# Power.net
KiCad netlist of a schematic drawn in Altium Designer
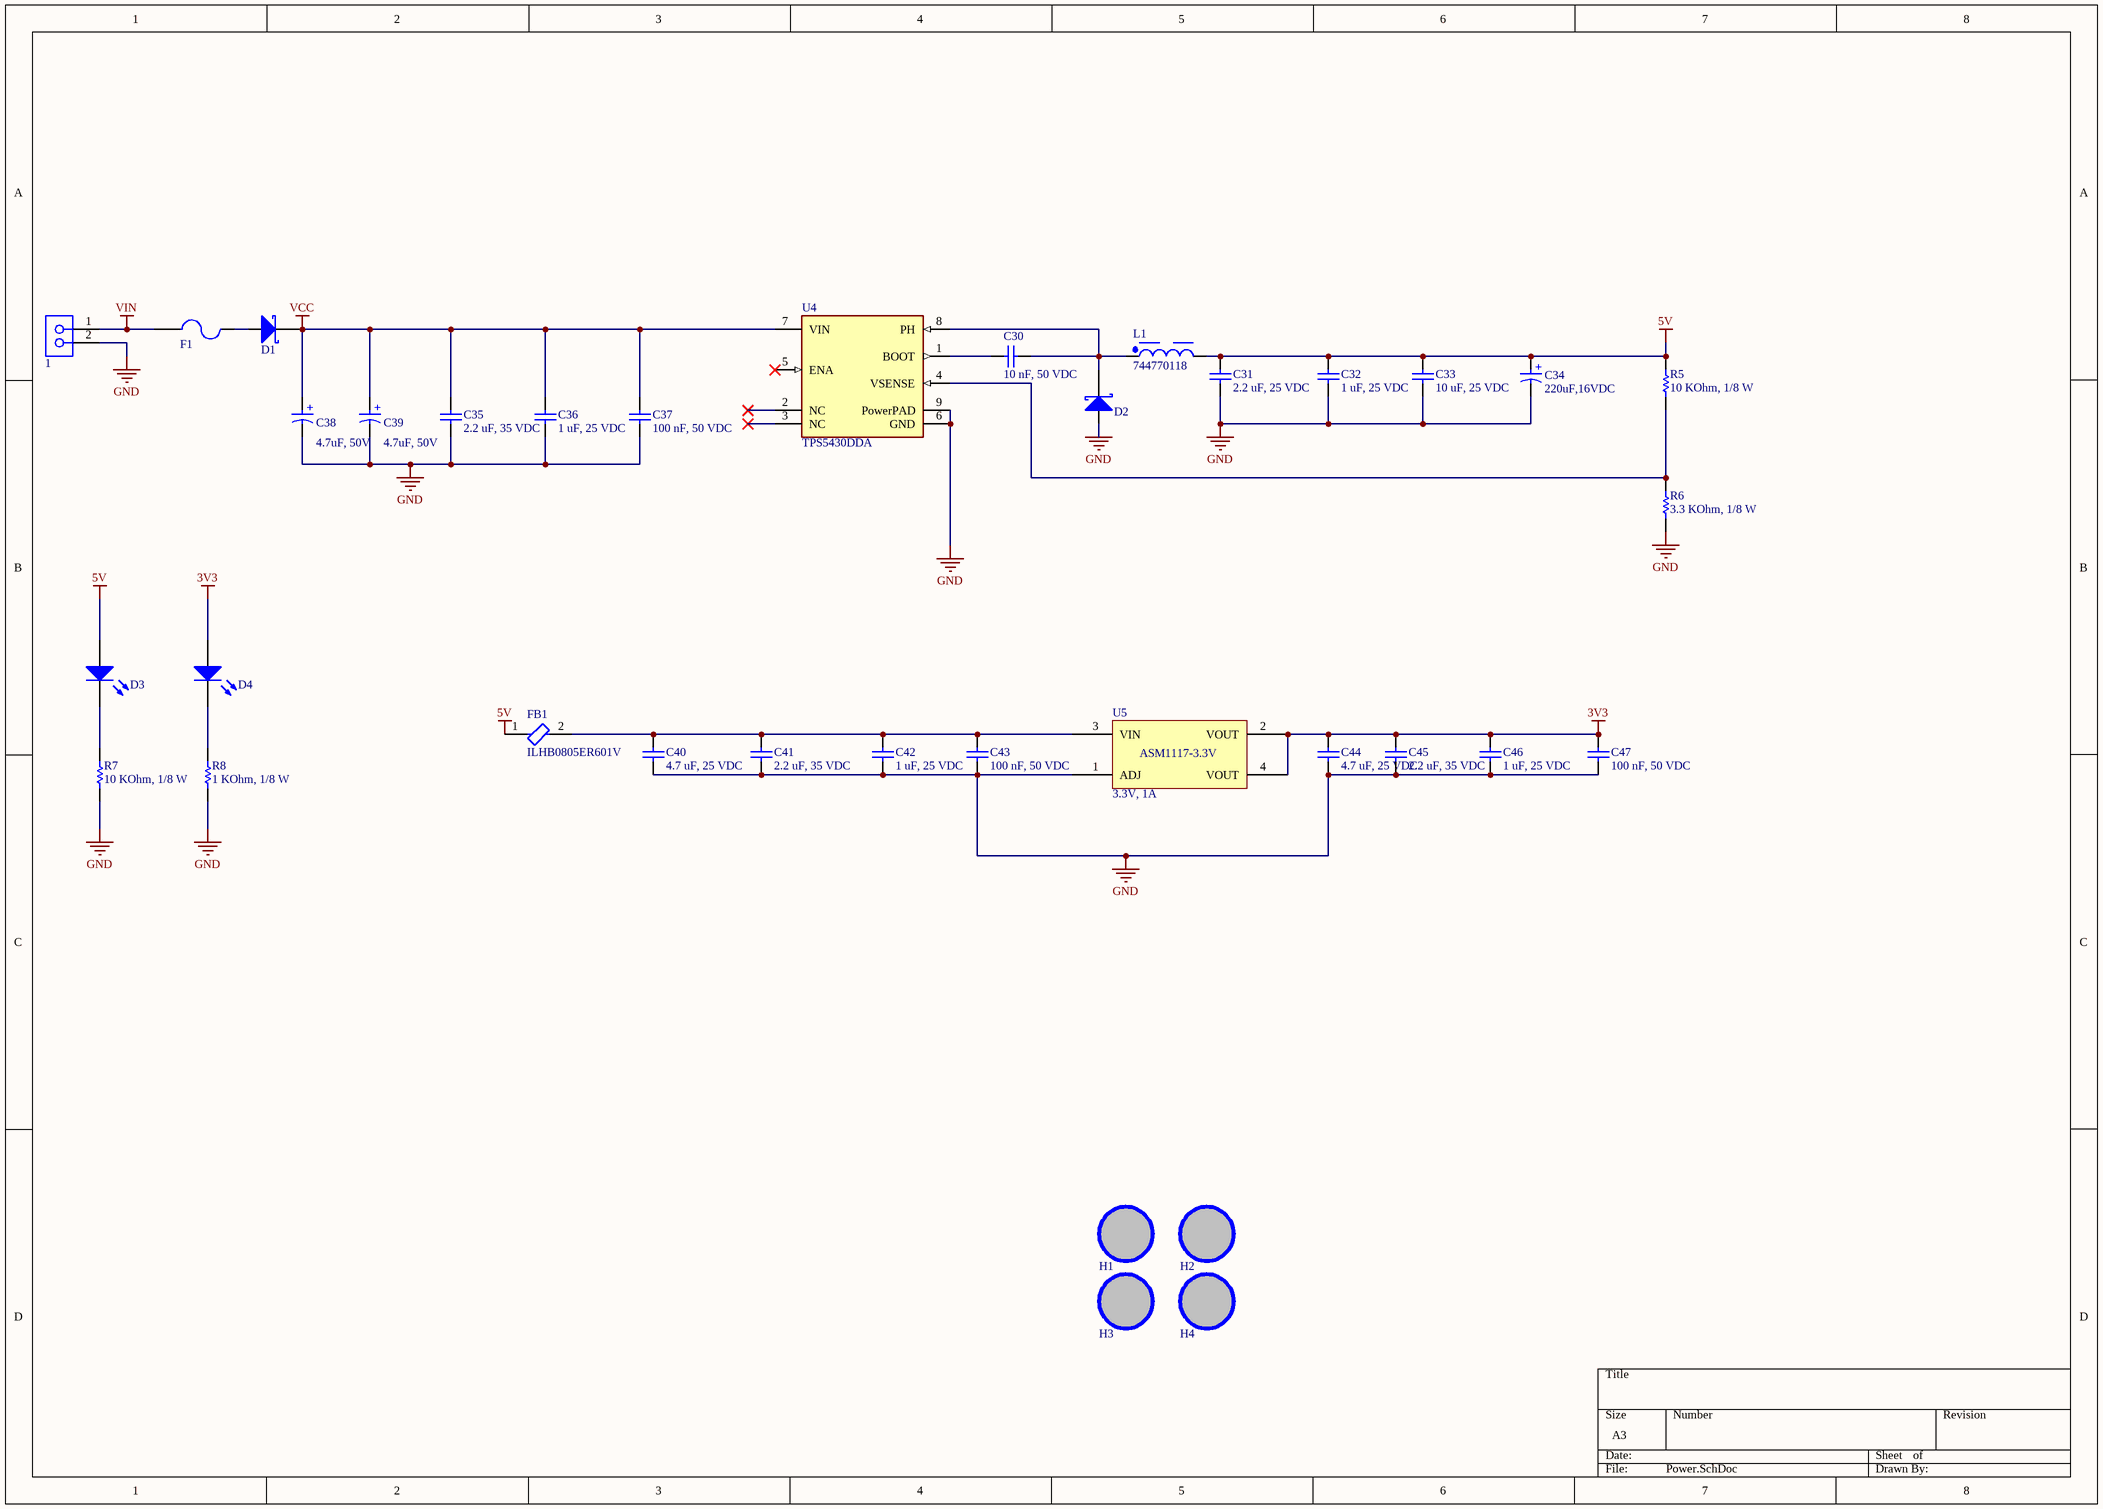
[diagram p0: Power.SchDoc]

(export (version "E")
  (design (tool "Eeschema 10.0.6"))
  (components
    (comp (ref "1")
      (value "4A, 300V")
      (footprint "691418420002")
      (description "WR-TBL Series 4184 45° Entry, THT, pitch 7.62mm, 2p")
      (fields
        (field (name "MANUFACTURER PART NUMBER") "691418420002")
        (field (name "MANUFACTURER") "Wurth Elektronik")
      )
      (libsource (lib "Altium_Terminal_Block") (part "691418420002"))
    )
    (comp (ref "C30")
      (value "10 nF, 50 VDC")
      (footprint "CAP_0805")
      (description "CAP, size 0805, 10 nF, 50 VDC")
      (fields (field (name "TOLERANCE") "+/-5%"))
      (libsource (lib "Altium_Ceramic_Cap") (part "0108051031050"))
    )
    (comp (ref "C31")
      (value "2.2 uF, 25 VDC")
      (footprint "CAP_0805")
      (description "CAP, size 0805, 2.2 uF, 25 VDC")
      (fields (field (name "TOLERANCE") "+/-10%"))
      (libsource (lib "Altium_Ceramic_Cap") (part "0108052251025"))
    )
    (comp (ref "C32")
      (value "1 uF, 25 VDC")
      (footprint "CAP_0805")
      (description "CAP, size 0805, 1 uF, 25 VDC")
      (fields (field (name "TOLERANCE") "+/-10%"))
      (libsource (lib "Altium_Ceramic_Cap") (part "0108051051025"))
    )
    (comp (ref "C33")
      (value "10 uF, 25 VDC")
      (footprint "CAP_0805")
      (description "CAP, size 0805, 10 uF, 25 VDC")
      (fields (field (name "TOLERANCE") "+/-10%"))
      (libsource (lib "Altium_Ceramic_Cap") (part "0108051061025"))
    )
    (comp (ref "C34")
      (value "220uF,16VDC")
      (footprint "WCAP-ASLI_D6.3H7.7")
      (description "V-Chip, D6.3 x H7.7mm, 220uF, 16V")
      (fields (field (name "MANUFACTURER") "Wurth Elektronik"))
      (libsource (lib "Altium_Alutinum_Cap") (part "865080345012"))
    )
    (comp (ref "C35")
      (value "2.2 uF, 35 VDC")
      (footprint "CAP_0805")
      (description "CAP, size 0805, 2.2 uF, 35 VDC")
      (fields (field (name "TOLERANCE") "+/-10%"))
      (libsource (lib "Altium_Ceramic_Cap") (part "0108052251035"))
    )
    (comp (ref "C36")
      (value "1 uF, 25 VDC")
      (footprint "CAP_0805")
      (description "CAP, size 0805, 1 uF, 25 VDC")
      (fields (field (name "TOLERANCE") "+/-10%"))
      (libsource (lib "Altium_Ceramic_Cap") (part "0108051051025"))
    )
    (comp (ref "C37")
      (value "100 nF, 50 VDC")
      (footprint "CAP_0805")
      (description "CAP, size 0805, 100 nF, 50 VDC")
      (fields (field (name "TOLERANCE") "+/-10%"))
      (libsource (lib "Altium_Ceramic_Cap") (part "0108051041050"))
    )
    (comp (ref "C38")
      (value "4.7uF, 50V")
      (footprint "WCAP-ASLI_D4H5.5")
      (description "V-Chip, D4 x H5.5mm, 4.7uF, 50V")
      (fields (field (name "MANUFACTURER") "Wurth Elektronik"))
      (libsource (lib "Altium_Alutinum_Cap") (part "865080640004"))
    )
    (comp (ref "C39")
      (value "4.7uF, 50V")
      (footprint "WCAP-ASLI_D4H5.5")
      (description "V-Chip, D4 x H5.5mm, 4.7uF, 50V")
      (fields (field (name "MANUFACTURER") "Wurth Elektronik"))
      (libsource (lib "Altium_Alutinum_Cap") (part "865080640004"))
    )
    (comp (ref "C40")
      (value "4.7 uF, 25 VDC")
      (footprint "CAP_0805")
      (description "CAP, size 0805, 4.7 uF, 25 VDC")
      (fields (field (name "TOLERANCE") "+/-10%"))
      (libsource (lib "Altium_Ceramic_Cap") (part "0108054751025"))
    )
    (comp (ref "C41")
      (value "2.2 uF, 35 VDC")
      (footprint "CAP_0805")
      (description "CAP, size 0805, 2.2 uF, 35 VDC")
      (fields (field (name "TOLERANCE") "+/-10%"))
      (libsource (lib "Altium_Ceramic_Cap") (part "0108052251035"))
    )
    (comp (ref "C42")
      (value "1 uF, 25 VDC")
      (footprint "CAP_0805")
      (description "CAP, size 0805, 1 uF, 25 VDC")
      (fields (field (name "TOLERANCE") "+/-10%"))
      (libsource (lib "Altium_Ceramic_Cap") (part "0108051051025"))
    )
    (comp (ref "C43")
      (value "100 nF, 50 VDC")
      (footprint "CAP_0805")
      (description "CAP, size 0805, 100 nF, 50 VDC")
      (fields (field (name "TOLERANCE") "+/-10%"))
      (libsource (lib "Altium_Ceramic_Cap") (part "0108051041050"))
    )
    (comp (ref "C44")
      (value "4.7 uF, 25 VDC")
      (footprint "CAP_0805")
      (description "CAP, size 0805, 4.7 uF, 25 VDC")
      (fields (field (name "TOLERANCE") "+/-10%"))
      (libsource (lib "Altium_Ceramic_Cap") (part "0108054751025"))
    )
    (comp (ref "C45")
      (value "2.2 uF, 35 VDC")
      (footprint "CAP_0805")
      (description "CAP, size 0805, 2.2 uF, 35 VDC")
      (fields (field (name "TOLERANCE") "+/-10%"))
      (libsource (lib "Altium_Ceramic_Cap") (part "0108052251035"))
    )
    (comp (ref "C46")
      (value "1 uF, 25 VDC")
      (footprint "CAP_0805")
      (description "CAP, size 0805, 1 uF, 25 VDC")
      (fields (field (name "TOLERANCE") "+/-10%"))
      (libsource (lib "Altium_Ceramic_Cap") (part "0108051051025"))
    )
    (comp (ref "C47")
      (value "100 nF, 50 VDC")
      (footprint "CAP_0805")
      (description "CAP, size 0805, 100 nF, 50 VDC")
      (fields (field (name "TOLERANCE") "+/-10%"))
      (libsource (lib "Altium_Ceramic_Cap") (part "0108051041050"))
    )
    (comp (ref "D1")
      (value "D Schottky")
      (footprint "SS34")
      (description "Schottky Diode")
      (fields (field (name "PUBLISHER") "Altium Limited"))
      (libsource (lib "Board_C24") (part "D Schottky"))
    )
    (comp (ref "D2")
      (value "D Schottky")
      (footprint "SS34")
      (description "Schottky Diode")
      (fields (field (name "PUBLISHER") "Altium Limited"))
      (libsource (lib "Board_C24") (part "D Schottky"))
    )
    (comp (ref "D3")
      (value "LED SMD")
      (footprint "LED_0805_Blue")
      (description "LED")
      (libsource (lib "Board_C24") (part "LED SMD"))
    )
    (comp (ref "D4")
      (value "LED SMD")
      (footprint "LED_0805_Blue")
      (description "LED")
      (libsource (lib "Board_C24") (part "LED SMD"))
    )
    (comp (ref "F1") (value "Fuse") (footprint "FUSE SMD") (libsource (lib "Board_C24") (part "Fuse")))
    (comp (ref "FB1")
      (value "ILHB0805ER601V")
      (footprint "FP-ILHB-0805-IPC_C")
      (description "FERRITE BEAD 600 OHM 0805 1LN")
      (fields
        (field (name "TOLERANCE") "25%")
        (field (name "OCTOPART") "https://octopart.com/ilhb0805er601v-vishay-39650184")
      )
      (libsource (lib "Altium Content Vault") (part "5f30dd21d616792df468990f7003faa"))
    )
    (comp (ref "H1")
      (value "Hole")
      (footprint "LO KHOAN 3MM")
      (description "Hole 3mm")
      (libsource (lib "Board_C24") (part "Hole"))
    )
    (comp (ref "H2")
      (value "Hole")
      (footprint "LO KHOAN 3MM")
      (description "Hole 3mm")
      (libsource (lib "Board_C24") (part "Hole"))
    )
    (comp (ref "H3")
      (value "Hole")
      (footprint "LO KHOAN 3MM")
      (description "Hole 3mm")
      (libsource (lib "Board_C24") (part "Hole"))
    )
    (comp (ref "H4")
      (value "Hole")
      (footprint "LO KHOAN 3MM")
      (description "Hole 3mm")
      (libsource (lib "Board_C24") (part "Hole"))
    )
    (comp (ref "L1")
      (value "744770118")
      (footprint "WE-PD_1280")
      (libsource (lib "Altium Content Vault") (part "Inductor - 2"))
    )
    (comp (ref "R5")
      (value "10 KOhm, 1/8 W")
      (footprint "RESISTOR_0805")
      (description "RES, size 0805, 10 KOhm, 1/8 W")
      (libsource (lib "Altium_Resistor") (part "0008051035"))
    )
    (comp (ref "R6")
      (value "3.3 KOhm, 1/8 W")
      (footprint "RESISTOR_0805")
      (description "RES, size 0805, 3.3 KOhm, 1/8 W")
      (libsource (lib "Altium_Resistor") (part "0008053325"))
    )
    (comp (ref "R7")
      (value "10 KOhm, 1/8 W")
      (footprint "RESISTOR_0805")
      (description "RES, size 0805, 10 KOhm, 1/8 W")
      (libsource (lib "Altium_Resistor") (part "0008051031"))
    )
    (comp (ref "R8")
      (value "1 KOhm, 1/8 W")
      (footprint "RESISTOR_0805")
      (description "RES, size 0805, 1 KOhm, 1/8 W")
      (libsource (lib "Altium_Resistor") (part "0008051025"))
    )
    (comp (ref "U4")
      (value "TPS5430DDA")
      (footprint "FP-DDA0008J-MFG")
      (description "IC REG BUCK ADJUSTABLE 3A 8SOPWR")
      (fields
        (field (name "MANUFACTURER") "Texas Instruments")
        (field (name "OCTOPART") "https://octopart.com/tps5430dda-texas+instruments-589977")
      )
      (libsource (lib "Altium Content Vault") (part "98da629940cea6febc5630bb55159f3"))
    )
    (comp (ref "U5")
      (value "3.3V, 1A")
      (footprint "AMS1117-3.3V SOT223")
      (description "AMS1117-3.3V, OUT 3.3V 1A.")
      (fields (field (name "MANUFACTURER") "AMS"))
      (libsource (lib "Altium_Power_Supply_IC") (part "AMS1117-3.3V"))
    )
  )
  (nets
    (net (code "1") (name "3V3") (class "Default")
      (node (ref "C44") (pin "2") (pinfunction "2_2") (pintype "passive"))
      (node (ref "C45") (pin "2") (pinfunction "2_2") (pintype "passive"))
      (node (ref "C46") (pin "2") (pinfunction "2_2") (pintype "passive"))
      (node (ref "C47") (pin "2") (pinfunction "2_2") (pintype "passive"))
      (node (ref "D4") (pin "1") (pinfunction "A_1") (pintype "passive"))
      (node (ref "U5") (pin "2") (pinfunction "VOUT_2") (pintype "passive"))
      (node (ref "U5") (pin "4") (pinfunction "VOUT_4") (pintype "power_in"))
    )
    (net (code "2") (name "5V") (class "Default")
      (node (ref "C31") (pin "2") (pinfunction "2_2") (pintype "passive"))
      (node (ref "C32") (pin "2") (pinfunction "2_2") (pintype "passive"))
      (node (ref "C33") (pin "2") (pinfunction "2_2") (pintype "passive"))
      (node (ref "C34") (pin "1") (pinfunction "P_1") (pintype "passive"))
      (node (ref "D3") (pin "1") (pinfunction "A_1") (pintype "passive"))
      (node (ref "FB1") (pin "1") (pinfunction "1_1") (pintype "passive"))
      (node (ref "L1") (pin "2") (pinfunction "2_2") (pintype "passive"))
      (node (ref "R5") (pin "2") (pinfunction "2_2") (pintype "passive"))
    )
    (net (code "3") (name "GND") (class "Default")
      (node (ref "1") (pin "2") (pinfunction "2_2") (pintype "passive"))
      (node (ref "C31") (pin "1") (pinfunction "1_1") (pintype "passive"))
      (node (ref "C32") (pin "1") (pinfunction "1_1") (pintype "passive"))
      (node (ref "C33") (pin "1") (pinfunction "1_1") (pintype "passive"))
      (node (ref "C34") (pin "2") (pinfunction "N_2") (pintype "passive"))
      (node (ref "C35") (pin "1") (pinfunction "1_1") (pintype "passive"))
      (node (ref "C36") (pin "1") (pinfunction "1_1") (pintype "passive"))
      (node (ref "C37") (pin "1") (pinfunction "1_1") (pintype "passive"))
      (node (ref "C38") (pin "2") (pinfunction "N_2") (pintype "passive"))
      (node (ref "C39") (pin "2") (pinfunction "N_2") (pintype "passive"))
      (node (ref "C40") (pin "1") (pinfunction "1_1") (pintype "passive"))
      (node (ref "C41") (pin "1") (pinfunction "1_1") (pintype "passive"))
      (node (ref "C42") (pin "1") (pinfunction "1_1") (pintype "passive"))
      (node (ref "C43") (pin "1") (pinfunction "1_1") (pintype "passive"))
      (node (ref "C44") (pin "1") (pinfunction "1_1") (pintype "passive"))
      (node (ref "C45") (pin "1") (pinfunction "1_1") (pintype "passive"))
      (node (ref "C46") (pin "1") (pinfunction "1_1") (pintype "passive"))
      (node (ref "C47") (pin "1") (pinfunction "1_1") (pintype "passive"))
      (node (ref "D2") (pin "1") (pinfunction "A_1") (pintype "passive"))
      (node (ref "R6") (pin "1") (pinfunction "1_1") (pintype "passive"))
      (node (ref "R7") (pin "1") (pinfunction "1_1") (pintype "passive"))
      (node (ref "R8") (pin "1") (pinfunction "1_1") (pintype "passive"))
      (node (ref "U4") (pin "6") (pinfunction "GND_6") (pintype "power_in"))
      (node (ref "U4") (pin "9") (pinfunction "PowerPAD_9") (pintype "power_in"))
      (node (ref "U5") (pin "1") (pinfunction "ADJ_1") (pintype "power_in"))
    )
    (net (code "4") (name "Net-(D1-A)") (class "Default")
      (node (ref "D1") (pin "1") (pinfunction "A_1") (pintype "passive"))
      (node (ref "F1") (pin "2") (pinfunction "2_2") (pintype "passive"))
    )
    (net (code "5") (name "Net-(D2-K)") (class "Default")
      (node (ref "C30") (pin "1") (pinfunction "1_1") (pintype "passive"))
      (node (ref "D2") (pin "2") (pinfunction "K_2") (pintype "passive"))
      (node (ref "L1") (pin "1") (pinfunction "1_1") (pintype "passive"))
      (node (ref "U4") (pin "8") (pinfunction "PH_8") (pintype "input"))
    )
    (net (code "6") (name "Net-(D3-K)") (class "Default")
      (node (ref "D3") (pin "2") (pinfunction "K_2") (pintype "passive"))
      (node (ref "R7") (pin "2") (pinfunction "2_2") (pintype "passive"))
    )
    (net (code "7") (name "Net-(D4-K)") (class "Default")
      (node (ref "D4") (pin "2") (pinfunction "K_2") (pintype "passive"))
      (node (ref "R8") (pin "2") (pinfunction "2_2") (pintype "passive"))
    )
    (net (code "8") (name "Net-(U4-BOOT)") (class "Default")
      (node (ref "C30") (pin "2") (pinfunction "2_2") (pintype "passive"))
      (node (ref "U4") (pin "1") (pinfunction "BOOT_1") (pintype "output"))
    )
    (net (code "9") (name "Net-(U4-VSENSE)") (class "Default")
      (node (ref "R5") (pin "1") (pinfunction "1_1") (pintype "passive"))
      (node (ref "R6") (pin "2") (pinfunction "2_2") (pintype "passive"))
      (node (ref "U4") (pin "4") (pinfunction "VSENSE_4") (pintype "input"))
    )
    (net (code "10") (name "Net-(U5-VIN)") (class "Default")
      (node (ref "C40") (pin "2") (pinfunction "2_2") (pintype "passive"))
      (node (ref "C41") (pin "2") (pinfunction "2_2") (pintype "passive"))
      (node (ref "C42") (pin "2") (pinfunction "2_2") (pintype "passive"))
      (node (ref "C43") (pin "2") (pinfunction "2_2") (pintype "passive"))
      (node (ref "FB1") (pin "2") (pinfunction "2_2") (pintype "passive"))
      (node (ref "U5") (pin "3") (pinfunction "VIN_3") (pintype "passive"))
    )
    (net (code "11") (name "VCC") (class "Default")
      (node (ref "C35") (pin "2") (pinfunction "2_2") (pintype "passive"))
      (node (ref "C36") (pin "2") (pinfunction "2_2") (pintype "passive"))
      (node (ref "C37") (pin "2") (pinfunction "2_2") (pintype "passive"))
      (node (ref "C38") (pin "1") (pinfunction "P_1") (pintype "passive"))
      (node (ref "C39") (pin "1") (pinfunction "P_1") (pintype "passive"))
      (node (ref "D1") (pin "2") (pinfunction "K_2") (pintype "passive"))
      (node (ref "U4") (pin "7") (pinfunction "VIN_7") (pintype "power_in"))
    )
    (net (code "12") (name "VIN") (class "Default")
      (node (ref "1") (pin "1") (pinfunction "1_1") (pintype "passive"))
      (node (ref "F1") (pin "1") (pinfunction "1_1") (pintype "passive"))
    )
    (net (code "13") (name "unconnected-(H1-Pad1)") (class "Default")
      (node (ref "H1") (pin "1") (pinfunction "1_1") (pintype "passive"))
    )
    (net (code "14") (name "unconnected-(H2-Pad1)") (class "Default")
      (node (ref "H2") (pin "1") (pinfunction "1_1") (pintype "passive"))
    )
    (net (code "15") (name "unconnected-(H3-Pad1)") (class "Default")
      (node (ref "H3") (pin "1") (pinfunction "1_1") (pintype "passive"))
    )
    (net (code "16") (name "unconnected-(H4-Pad1)") (class "Default")
      (node (ref "H4") (pin "1") (pinfunction "1_1") (pintype "passive"))
    )
    (net (code "17") (name "unconnected-(U4-ENA-Pad5)") (class "Default")
      (node (ref "U4") (pin "5") (pinfunction "ENA_5") (pintype "input+no_connect"))
    )
    (net (code "18") (name "unconnected-(U4-NC-Pad2)") (class "Default")
      (node (ref "U4") (pin "2") (pinfunction "NC_2") (pintype "passive+no_connect"))
    )
    (net (code "19") (name "unconnected-(U4-NC-Pad3)") (class "Default")
      (node (ref "U4") (pin "3") (pinfunction "NC_3") (pintype "passive+no_connect"))
    )
  )
)
